# ProPrj_SBL_V1_2026-03-12.net
KiCad netlist of a schematic drawn in EasyEDA Pro
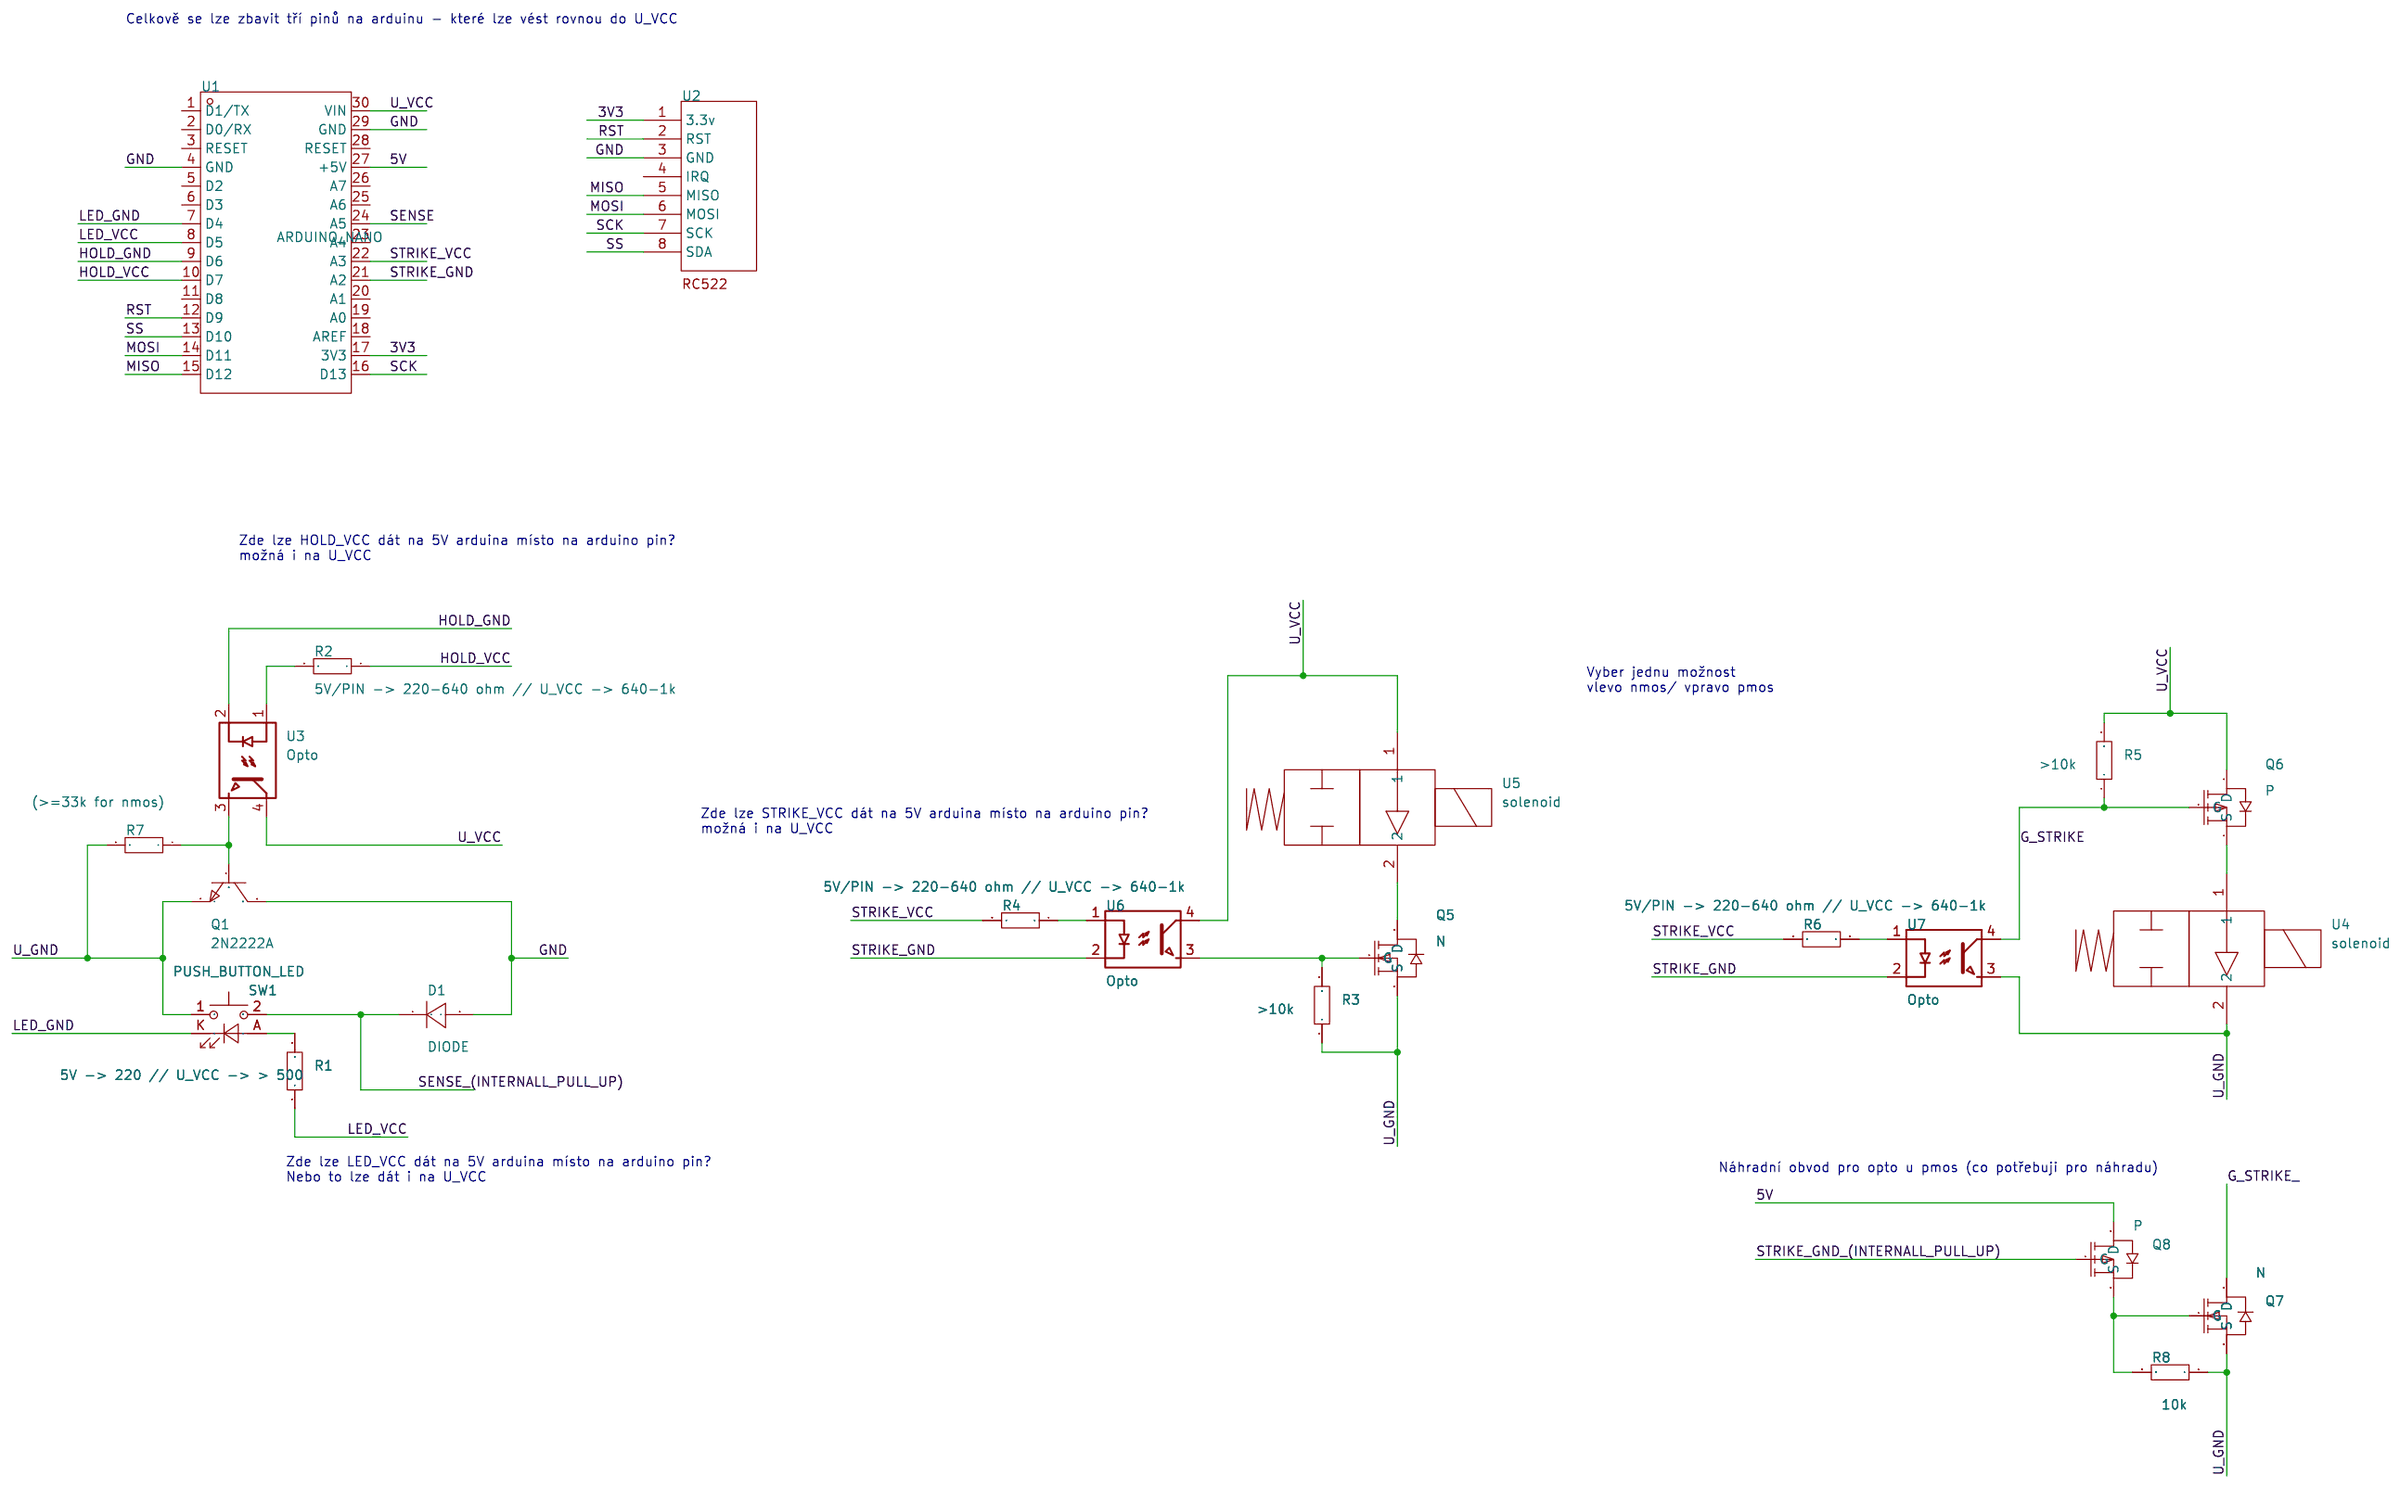
[diagram p0: schematic sheet]

(export (version "E")
  (design (tool "Eeschema 10.0.6"))
  (components
    (comp (ref "D1")
      (value "DIODE")
      (fields (field (name "Manufacturer Part") "M7") (field (name "Manufacturer") "MDD"))
      (libsource (lib "easyedapro") (part "DIODE"))
    )
    (comp (ref "Q1")
      (value "2N2222A")
      (footprint "easyedapro:SOT-23-3_L2.9-W1.3-P1.90-LS2.4-BR")
      (fields (field (name "Manufacturer") "CJ(江苏长电/长晶)"))
      (libsource (lib "easyedapro") (part "SS8050_C2150"))
    )
    (comp (ref "Q5")
      (value "N")
      (footprint "easyedapro:SOT-23-3_L2.9-W1.3-P1.90-LS2.4-BR")
      (libsource (lib "easyedapro") (part "N_MOS"))
    )
    (comp (ref "Q6")
      (value "P")
      (footprint "easyedapro:SOT-23_L2.9-W1.3-P1.90-LS2.4-BR")
      (libsource (lib "easyedapro") (part "P_MOS"))
    )
    (comp (ref "Q7")
      (value "N")
      (footprint "easyedapro:SOT-23-3_L2.9-W1.3-P1.90-LS2.4-BR")
      (libsource (lib "easyedapro") (part "N_MOS"))
    )
    (comp (ref "Q8")
      (value "P")
      (footprint "easyedapro:SOT-23_L2.9-W1.3-P1.90-LS2.4-BR")
      (libsource (lib "easyedapro") (part "P_MOS"))
    )
    (comp (ref "R1")
      (value "5V -> 220 // U_VCC -> > 500")
      (footprint "easyedapro:R0603")
      (libsource (lib "easyedapro") (part "Res"))
    )
    (comp (ref "R2")
      (value "5V/PIN -> 220-640 ohm // U_VCC -> 640-1k")
      (footprint "easyedapro:R0603")
      (libsource (lib "easyedapro") (part "Res"))
    )
    (comp (ref "R3")
      (value ">10k")
      (footprint "easyedapro:R0603")
      (libsource (lib "easyedapro") (part "Res"))
    )
    (comp (ref "R4")
      (value "5V/PIN -> 220-640 ohm // U_VCC -> 640-1k")
      (footprint "easyedapro:R0603")
      (libsource (lib "easyedapro") (part "Res"))
    )
    (comp (ref "R5")
      (value ">10k")
      (footprint "easyedapro:R0603")
      (libsource (lib "easyedapro") (part "Res"))
    )
    (comp (ref "R6")
      (value "5V/PIN -> 220-640 ohm // U_VCC -> 640-1k")
      (footprint "easyedapro:R0603")
      (libsource (lib "easyedapro") (part "Res"))
    )
    (comp (ref "R7")
      (value "(>=33k for nmos)")
      (footprint "easyedapro:R0603")
      (libsource (lib "easyedapro") (part "Res"))
    )
    (comp (ref "R8") (value "10k") (footprint "easyedapro:R0603") (libsource (lib "easyedapro") (part "Res")))
    (comp (ref "SW1") (value "PUSH_BUTTON_LED") (libsource (lib "easyedapro") (part "PUSH_BUTTON_LED_12MM")))
    (comp (ref "U1")
      (value "ARDUINO_NANO")
      (footprint "easyedapro:ARDUINO_NANO_SMD_V3")
      (libsource (lib "easyedapro") (part "ARDUINO_NANO_SMD_V3"))
    )
    (comp (ref "U2") (value "~") (footprint "easyedapro:RC522") (libsource (lib "easyedapro") (part "RC522")))
    (comp (ref "U3") (value "Opto") (libsource (lib "easyedapro") (part "Opto")))
    (comp (ref "U4") (value "solenoid") (libsource (lib "easyedapro") (part "solenoid")))
    (comp (ref "U5") (value "solenoid") (libsource (lib "easyedapro") (part "solenoid")))
    (comp (ref "U6") (value "Opto") (libsource (lib "easyedapro") (part "Opto")))
    (comp (ref "U7") (value "Opto") (libsource (lib "easyedapro") (part "Opto")))
  )
  (nets
    (net (code "1") (name "/3V3") (class "Default")
      (node (ref "U1") (pin "17") (pinfunction "3V3_17") (pintype "input"))
      (node (ref "U2") (pin "1") (pinfunction "3.3v_1") (pintype "input"))
    )
    (net (code "2") (name "/5V") (class "Default")
      (node (ref "Q8") (pin "3") (pinfunction "D_3") (pintype "input"))
      (node (ref "U1") (pin "27") (pinfunction "+5V_27") (pintype "input"))
    )
    (net (code "3") (name "/GND") (class "Default")
      (node (ref "D1") (pin "2") (pinfunction "A_2") (pintype "unspecified"))
      (node (ref "Q1") (pin "3") (pinfunction "C_3") (pintype "input"))
      (node (ref "U1") (pin "29") (pinfunction "GND_29") (pintype "input"))
      (node (ref "U1") (pin "4") (pinfunction "GND_4") (pintype "input"))
      (node (ref "U2") (pin "3") (pinfunction "GND_3") (pintype "input"))
    )
    (net (code "4") (name "/G_STRIKE") (class "Default")
      (node (ref "Q6") (pin "1") (pinfunction "G_1") (pintype "input"))
      (node (ref "R5") (pin "1") (pinfunction "1_1") (pintype "input"))
      (node (ref "U7") (pin "4") (pintype "unspecified"))
    )
    (net (code "5") (name "/G_STRIKE_") (class "Default")
      (node (ref "Q7") (pin "3") (pinfunction "D_3") (pintype "input"))
    )
    (net (code "6") (name "/HOLD_GND") (class "Default")
      (node (ref "U1") (pin "9") (pinfunction "D6_9") (pintype "input"))
      (node (ref "U3") (pin "2") (pintype "unspecified"))
    )
    (net (code "7") (name "/HOLD_VCC") (class "Default")
      (node (ref "R2") (pin "1") (pinfunction "1_1") (pintype "input"))
      (node (ref "U1") (pin "10") (pinfunction "D7_10") (pintype "input"))
    )
    (net (code "8") (name "/LED_GND") (class "Default")
      (node (ref "SW1") (pin "K") (pinfunction "K_K") (pintype "unspecified"))
      (node (ref "U1") (pin "7") (pinfunction "D4_7") (pintype "input"))
    )
    (net (code "9") (name "/LED_VCC") (class "Default")
      (node (ref "R1") (pin "1") (pinfunction "1_1") (pintype "input"))
      (node (ref "U1") (pin "8") (pinfunction "D5_8") (pintype "input"))
    )
    (net (code "10") (name "/MISO") (class "Default")
      (node (ref "U1") (pin "15") (pinfunction "D12_15") (pintype "input"))
      (node (ref "U2") (pin "5") (pinfunction "MISO_5") (pintype "input"))
    )
    (net (code "11") (name "/MOSI") (class "Default")
      (node (ref "U1") (pin "14") (pinfunction "D11_14") (pintype "input"))
      (node (ref "U2") (pin "6") (pinfunction "MOSI_6") (pintype "input"))
    )
    (net (code "12") (name "/RST") (class "Default")
      (node (ref "U1") (pin "12") (pinfunction "D9_12") (pintype "input"))
      (node (ref "U2") (pin "2") (pinfunction "RST_2") (pintype "input"))
    )
    (net (code "13") (name "/SCK") (class "Default")
      (node (ref "U1") (pin "16") (pinfunction "D13_16") (pintype "input"))
      (node (ref "U2") (pin "7") (pinfunction "SCK_7") (pintype "input"))
    )
    (net (code "14") (name "/SENSE") (class "Default")
      (node (ref "U1") (pin "24") (pinfunction "A5_24") (pintype "input"))
    )
    (net (code "15") (name "/SENSE_(INTERNALL_PULL_UP)") (class "Default")
      (node (ref "D1") (pin "1") (pinfunction "K_1") (pintype "unspecified"))
      (node (ref "SW1") (pin "2") (pinfunction "2_2") (pintype "unspecified"))
    )
    (net (code "16") (name "/SS") (class "Default")
      (node (ref "U1") (pin "13") (pinfunction "D10_13") (pintype "input"))
      (node (ref "U2") (pin "8") (pinfunction "SDA_8") (pintype "input"))
    )
    (net (code "17") (name "/STRIKE_GND") (class "Default")
      (node (ref "U1") (pin "21") (pinfunction "A2_21") (pintype "input"))
      (node (ref "U6") (pin "2") (pintype "unspecified"))
      (node (ref "U7") (pin "2") (pintype "unspecified"))
    )
    (net (code "18") (name "/STRIKE_GND_(INTERNALL_PULL_UP)") (class "Default")
      (node (ref "Q8") (pin "1") (pinfunction "G_1") (pintype "input"))
    )
    (net (code "19") (name "/STRIKE_VCC") (class "Default")
      (node (ref "R4") (pin "2") (pinfunction "2_2") (pintype "input"))
      (node (ref "R6") (pin "2") (pinfunction "2_2") (pintype "input"))
      (node (ref "U1") (pin "22") (pinfunction "A3_22") (pintype "input"))
    )
    (net (code "20") (name "/U_GND") (class "Default")
      (node (ref "Q1") (pin "2") (pinfunction "E_2") (pintype "input"))
      (node (ref "Q5") (pin "2") (pinfunction "S_2") (pintype "input"))
      (node (ref "Q7") (pin "2") (pinfunction "S_2") (pintype "input"))
      (node (ref "R3") (pin "1") (pinfunction "1_1") (pintype "input"))
      (node (ref "R7") (pin "2") (pinfunction "2_2") (pintype "input"))
      (node (ref "R8") (pin "1") (pinfunction "1_1") (pintype "input"))
      (node (ref "SW1") (pin "1") (pinfunction "1_1") (pintype "unspecified"))
      (node (ref "U4") (pin "2") (pinfunction "2_2") (pintype "unspecified"))
      (node (ref "U7") (pin "3") (pintype "unspecified"))
    )
    (net (code "21") (name "/U_VCC") (class "Default")
      (node (ref "Q6") (pin "3") (pinfunction "D_3") (pintype "input"))
      (node (ref "R5") (pin "2") (pinfunction "2_2") (pintype "input"))
      (node (ref "U1") (pin "30") (pinfunction "VIN_30") (pintype "input"))
      (node (ref "U3") (pin "4") (pintype "unspecified"))
      (node (ref "U5") (pin "1") (pinfunction "1_1") (pintype "unspecified"))
      (node (ref "U6") (pin "4") (pintype "unspecified"))
    )
    (net (code "22") (name "Net-(Q1-B)") (class "Default")
      (node (ref "Q1") (pin "1") (pinfunction "B_1") (pintype "input"))
      (node (ref "R7") (pin "1") (pinfunction "1_1") (pintype "input"))
      (node (ref "U3") (pin "3") (pintype "unspecified"))
    )
    (net (code "23") (name "Net-(Q5-D)") (class "Default")
      (node (ref "Q5") (pin "3") (pinfunction "D_3") (pintype "input"))
      (node (ref "U5") (pin "2") (pinfunction "2_2") (pintype "unspecified"))
    )
    (net (code "24") (name "Net-(Q5-G)") (class "Default")
      (node (ref "Q5") (pin "1") (pinfunction "G_1") (pintype "input"))
      (node (ref "R3") (pin "2") (pinfunction "2_2") (pintype "input"))
      (node (ref "U6") (pin "3") (pintype "unspecified"))
    )
    (net (code "25") (name "Net-(Q6-S)") (class "Default")
      (node (ref "Q6") (pin "2") (pinfunction "S_2") (pintype "input"))
      (node (ref "U4") (pin "1") (pinfunction "1_1") (pintype "unspecified"))
    )
    (net (code "26") (name "Net-(Q7-G)") (class "Default")
      (node (ref "Q7") (pin "1") (pinfunction "G_1") (pintype "input"))
      (node (ref "Q8") (pin "2") (pinfunction "S_2") (pintype "input"))
      (node (ref "R8") (pin "2") (pinfunction "2_2") (pintype "input"))
    )
    (net (code "27") (name "Net-(R1-Pad2)") (class "Default")
      (node (ref "R1") (pin "2") (pinfunction "2_2") (pintype "input"))
      (node (ref "SW1") (pin "A") (pinfunction "A_A") (pintype "unspecified"))
    )
    (net (code "28") (name "Net-(R2-Pad2)") (class "Default")
      (node (ref "R2") (pin "2") (pinfunction "2_2") (pintype "input"))
      (node (ref "U3") (pin "1") (pintype "unspecified"))
    )
    (net (code "29") (name "Net-(R4-Pad1)") (class "Default")
      (node (ref "R4") (pin "1") (pinfunction "1_1") (pintype "input"))
      (node (ref "U6") (pin "1") (pintype "unspecified"))
    )
    (net (code "30") (name "Net-(R6-Pad1)") (class "Default")
      (node (ref "R6") (pin "1") (pinfunction "1_1") (pintype "input"))
      (node (ref "U7") (pin "1") (pintype "unspecified"))
    )
    (net (code "31") (name "unconnected-(U1-A0-Pad19)") (class "Default")
      (node (ref "U1") (pin "19") (pinfunction "A0_19") (pintype "input"))
    )
    (net (code "32") (name "unconnected-(U1-A1-Pad20)") (class "Default")
      (node (ref "U1") (pin "20") (pinfunction "A1_20") (pintype "input"))
    )
    (net (code "33") (name "unconnected-(U1-A4-Pad23)") (class "Default")
      (node (ref "U1") (pin "23") (pinfunction "A4_23") (pintype "input"))
    )
    (net (code "34") (name "unconnected-(U1-A6-Pad25)") (class "Default")
      (node (ref "U1") (pin "25") (pinfunction "A6_25") (pintype "input"))
    )
    (net (code "35") (name "unconnected-(U1-A7-Pad26)") (class "Default")
      (node (ref "U1") (pin "26") (pinfunction "A7_26") (pintype "input"))
    )
    (net (code "36") (name "unconnected-(U1-AREF-Pad18)") (class "Default")
      (node (ref "U1") (pin "18") (pinfunction "AREF_18") (pintype "input"))
    )
    (net (code "37") (name "unconnected-(U1-D0{slash}RX-Pad2)") (class "Default")
      (node (ref "U1") (pin "2") (pinfunction "D0/RX_2") (pintype "input"))
    )
    (net (code "38") (name "unconnected-(U1-D1{slash}TX-Pad1)") (class "Default")
      (node (ref "U1") (pin "1") (pinfunction "D1/TX_1") (pintype "input"))
    )
    (net (code "39") (name "unconnected-(U1-D2-Pad5)") (class "Default")
      (node (ref "U1") (pin "5") (pinfunction "D2_5") (pintype "input"))
    )
    (net (code "40") (name "unconnected-(U1-D3-Pad6)") (class "Default")
      (node (ref "U1") (pin "6") (pinfunction "D3_6") (pintype "input"))
    )
    (net (code "41") (name "unconnected-(U1-D8-Pad11)") (class "Default")
      (node (ref "U1") (pin "11") (pinfunction "D8_11") (pintype "input"))
    )
    (net (code "42") (name "unconnected-(U1-RESET-Pad3)") (class "Default")
      (node (ref "U1") (pin "3") (pinfunction "RESET_3") (pintype "input"))
    )
    (net (code "43") (name "unconnected-(U1-RESET-Pad28)") (class "Default")
      (node (ref "U1") (pin "28") (pinfunction "RESET_28") (pintype "input"))
    )
    (net (code "44") (name "unconnected-(U2-IRQ-Pad4)") (class "Default")
      (node (ref "U2") (pin "4") (pinfunction "IRQ_4") (pintype "input"))
    )
  )
)
